# easyeda_dice.net
KiCad netlist of a schematic drawn in EasyEDA
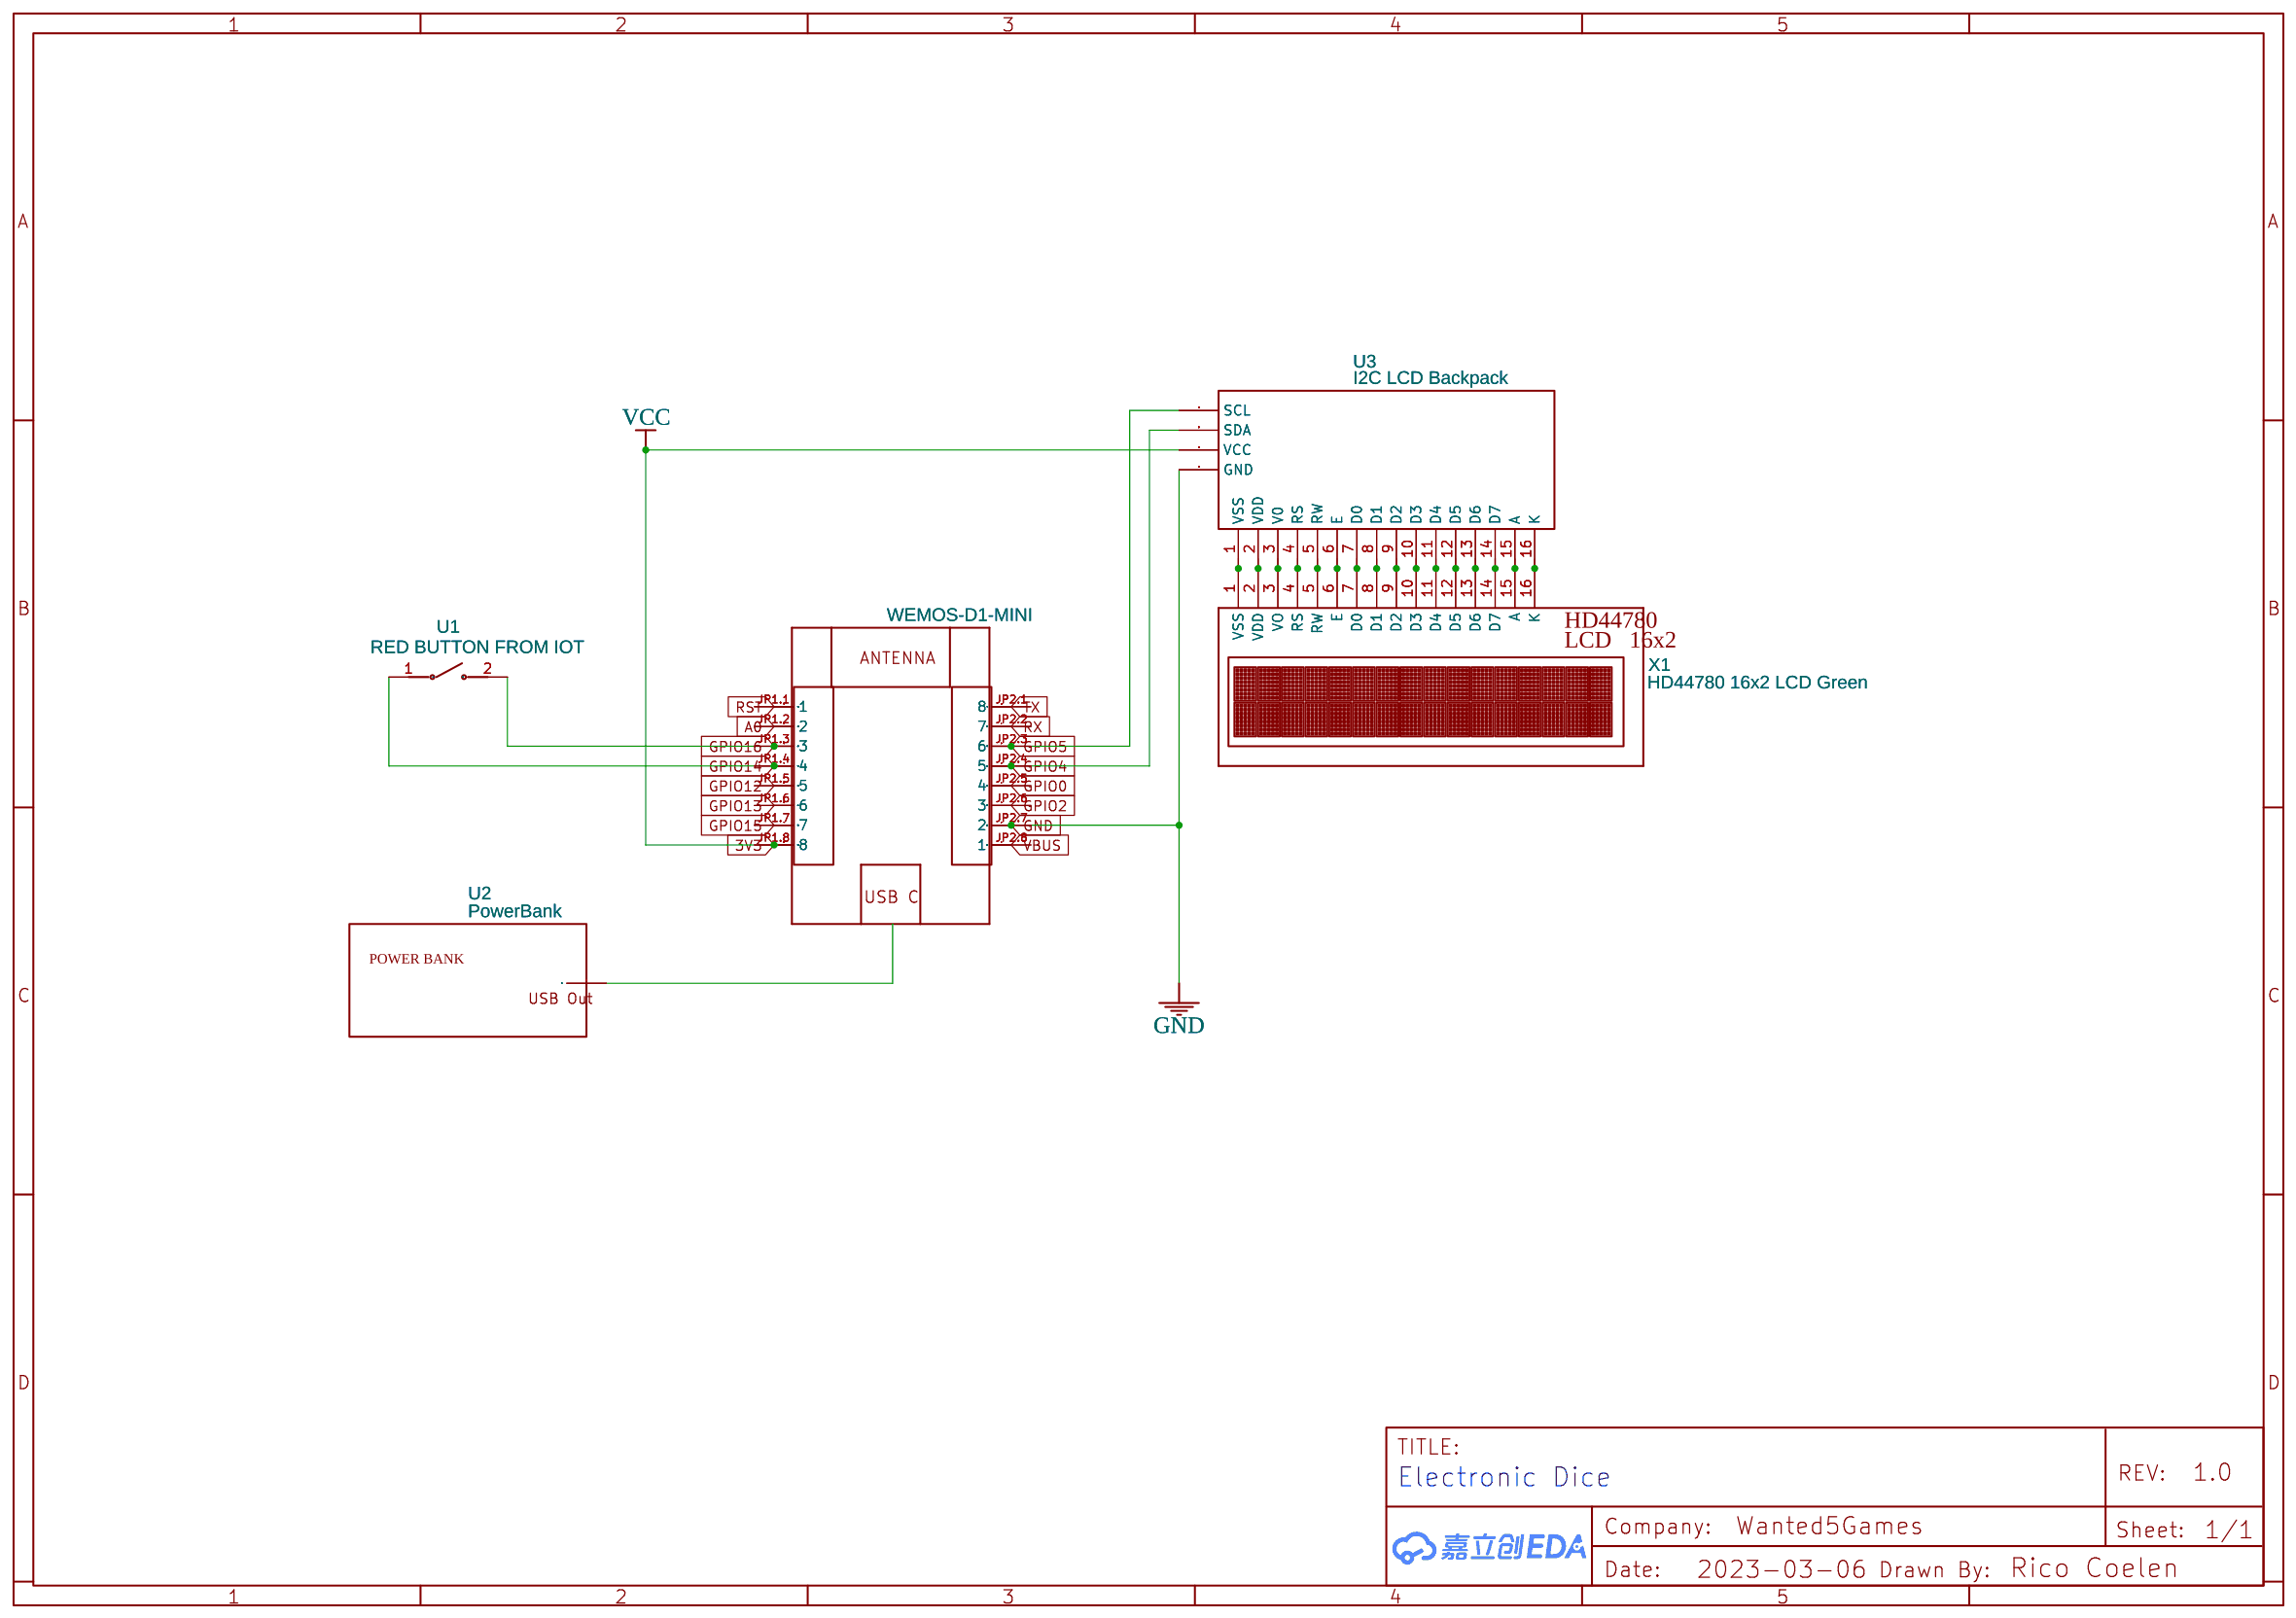
[diagram p0: schematic sheet]

(export (version "E")
  (design (tool "Eeschema 10.0.6"))
  (components
    (comp (ref "1") (value "WEMOS-D1-MINI") (libsource (lib "") (part "WEMOS-D1-MINI")))
    (comp (ref "H1")
      (value "HDR-F-2.54_1x8")
      (fields (field (name "BOM_Supplier Part") "C225505"))
      (libsource (lib "") (part "HDR-F-2.54_1x8_1"))
    )
    (comp (ref "H2")
      (value "HDR-F-2.54_1x8")
      (fields (field (name "BOM_Supplier Part") "C225505"))
      (libsource (lib "") (part "HDR-F-2.54_1x8"))
    )
    (comp (ref "U1")
      (value "RED BUTTON FROM IOT")
      (fields
        (field (name "BOM_Manufacturer Part") "BUTTON")
        (field (name "BOM_Supplier Part") "C9900015607")
      )
      (libsource (lib "") (part "BUTTON"))
    )
    (comp (ref "U2") (value "PowerBank") (libsource (lib "") (part "PowerBank")))
    (comp (ref "U3")
      (value "I2C LCD Backpack")
      (fields (field (name "BOM_Manufacturer Part") "I2C Bus Converter"))
      (libsource (lib "") (part "I2C LCD Backpack"))
    )
    (comp (ref "X1")
      (value "HD44780 16x2 LCD Green")
      (fields (field (name "BOM_Manufacturer Part") "HD44780U"))
      (libsource (lib "") (part "HD44780 16x2 LCD Green"))
    )
  )
  (nets
    (net (code "1") (name "3V3") (class "Default")
      (node (ref "H1") (pin "8") (pinfunction "8_8") (pintype "unspecified"))
      (node (ref "U3") (pin "18") (pinfunction "VCC_18") (pintype "unspecified"))
    )
    (net (code "2") (name "A0") (class "Default")
      (node (ref "H1") (pin "2") (pinfunction "2_2") (pintype "unspecified"))
    )
    (net (code "3") (name "GND") (class "Default")
      (node (ref "H2") (pin "2") (pinfunction "2_2") (pintype "unspecified"))
      (node (ref "U3") (pin "17") (pinfunction "GND_17") (pintype "unspecified"))
    )
    (net (code "4") (name "GPIO0") (class "Default")
      (node (ref "H2") (pin "4") (pinfunction "4_4") (pintype "unspecified"))
    )
    (net (code "5") (name "GPIO2") (class "Default")
      (node (ref "H2") (pin "3") (pinfunction "3_3") (pintype "unspecified"))
    )
    (net (code "6") (name "GPIO4") (class "Default")
      (node (ref "H2") (pin "5") (pinfunction "5_5") (pintype "unspecified"))
      (node (ref "U3") (pin "19") (pinfunction "SDA_19") (pintype "unspecified"))
    )
    (net (code "7") (name "GPIO5") (class "Default")
      (node (ref "H2") (pin "6") (pinfunction "6_6") (pintype "unspecified"))
      (node (ref "U3") (pin "20") (pinfunction "SCL_20") (pintype "unspecified"))
    )
    (net (code "8") (name "GPIO12") (class "Default")
      (node (ref "H1") (pin "5") (pinfunction "5_5") (pintype "unspecified"))
    )
    (net (code "9") (name "GPIO13") (class "Default")
      (node (ref "H1") (pin "6") (pinfunction "6_6") (pintype "unspecified"))
    )
    (net (code "10") (name "GPIO14") (class "Default")
      (node (ref "H1") (pin "4") (pinfunction "4_4") (pintype "unspecified"))
      (node (ref "U1") (pin "1") (pinfunction "1_1") (pintype "unspecified"))
    )
    (net (code "11") (name "GPIO15") (class "Default")
      (node (ref "H1") (pin "7") (pinfunction "7_7") (pintype "unspecified"))
    )
    (net (code "12") (name "GPIO16") (class "Default")
      (node (ref "H1") (pin "3") (pinfunction "3_3") (pintype "unspecified"))
      (node (ref "U1") (pin "2") (pinfunction "2_2") (pintype "unspecified"))
    )
    (net (code "13") (name "Net-(U3-A)") (class "Default")
      (node (ref "U3") (pin "15") (pinfunction "A_15") (pintype "unspecified"))
      (node (ref "X1") (pin "15") (pinfunction "A_15") (pintype "unspecified"))
    )
    (net (code "14") (name "Net-(U3-D0)") (class "Default")
      (node (ref "U3") (pin "7") (pinfunction "D0_7") (pintype "unspecified"))
      (node (ref "X1") (pin "7") (pinfunction "D0_7") (pintype "bidirectional"))
    )
    (net (code "15") (name "Net-(U3-D1)") (class "Default")
      (node (ref "U3") (pin "8") (pinfunction "D1_8") (pintype "unspecified"))
      (node (ref "X1") (pin "8") (pinfunction "D1_8") (pintype "bidirectional"))
    )
    (net (code "16") (name "Net-(U3-D2)") (class "Default")
      (node (ref "U3") (pin "9") (pinfunction "D2_9") (pintype "unspecified"))
      (node (ref "X1") (pin "9") (pinfunction "D2_9") (pintype "bidirectional"))
    )
    (net (code "17") (name "Net-(U3-D3)") (class "Default")
      (node (ref "U3") (pin "10") (pinfunction "D3_10") (pintype "unspecified"))
      (node (ref "X1") (pin "10") (pinfunction "D3_10") (pintype "bidirectional"))
    )
    (net (code "18") (name "Net-(U3-D4)") (class "Default")
      (node (ref "U3") (pin "11") (pinfunction "D4_11") (pintype "unspecified"))
      (node (ref "X1") (pin "11") (pinfunction "D4_11") (pintype "bidirectional"))
    )
    (net (code "19") (name "Net-(U3-D5)") (class "Default")
      (node (ref "U3") (pin "12") (pinfunction "D5_12") (pintype "unspecified"))
      (node (ref "X1") (pin "12") (pinfunction "D5_12") (pintype "bidirectional"))
    )
    (net (code "20") (name "Net-(U3-D6)") (class "Default")
      (node (ref "U3") (pin "13") (pinfunction "D6_13") (pintype "unspecified"))
      (node (ref "X1") (pin "13") (pinfunction "D6_13") (pintype "bidirectional"))
    )
    (net (code "21") (name "Net-(U3-D7)") (class "Default")
      (node (ref "U3") (pin "14") (pinfunction "D7_14") (pintype "unspecified"))
      (node (ref "X1") (pin "14") (pinfunction "D7_14") (pintype "bidirectional"))
    )
    (net (code "22") (name "Net-(U3-E)") (class "Default")
      (node (ref "U3") (pin "6") (pinfunction "E_6") (pintype "unspecified"))
      (node (ref "X1") (pin "6") (pinfunction "E_6") (pintype "bidirectional"))
    )
    (net (code "23") (name "Net-(U3-K)") (class "Default")
      (node (ref "U3") (pin "16") (pinfunction "K_16") (pintype "unspecified"))
      (node (ref "X1") (pin "16") (pinfunction "K_16") (pintype "unspecified"))
    )
    (net (code "24") (name "Net-(U3-RS)") (class "Default")
      (node (ref "U3") (pin "4") (pinfunction "RS_4") (pintype "unspecified"))
      (node (ref "X1") (pin "4") (pinfunction "RS_4") (pintype "bidirectional"))
    )
    (net (code "25") (name "Net-(U3-RW)") (class "Default")
      (node (ref "U3") (pin "5") (pinfunction "RW_5") (pintype "unspecified"))
      (node (ref "X1") (pin "5") (pinfunction "RW_5") (pintype "bidirectional"))
    )
    (net (code "26") (name "Net-(U3-V0)") (class "Default")
      (node (ref "U3") (pin "3") (pinfunction "V0_3") (pintype "unspecified"))
      (node (ref "X1") (pin "3") (pinfunction "VO_3") (pintype "passive"))
    )
    (net (code "27") (name "Net-(U3-VDD)") (class "Default")
      (node (ref "U3") (pin "2") (pinfunction "VDD_2") (pintype "unspecified"))
      (node (ref "X1") (pin "2") (pinfunction "VDD_2") (pintype "passive"))
    )
    (net (code "28") (name "Net-(U3-VSS)") (class "Default")
      (node (ref "U3") (pin "1") (pinfunction "VSS_1") (pintype "unspecified"))
      (node (ref "X1") (pin "1") (pinfunction "VSS_1") (pintype "passive"))
    )
    (net (code "29") (name "RST") (class "Default")
      (node (ref "H1") (pin "1") (pinfunction "1_1") (pintype "unspecified"))
    )
    (net (code "30") (name "RX") (class "Default")
      (node (ref "H2") (pin "7") (pinfunction "7_7") (pintype "unspecified"))
    )
    (net (code "31") (name "TX") (class "Default")
      (node (ref "H2") (pin "8") (pinfunction "8_8") (pintype "unspecified"))
    )
    (net (code "32") (name "VBUS") (class "Default")
      (node (ref "H2") (pin "1") (pinfunction "1_1") (pintype "unspecified"))
    )
    (net (code "33") (name "unconnected-(1-3V3-PadJP1.8)") (class "Default")
      (node (ref "1") (pin "JP1.8") (pinfunction "3V3_JP1.8") (pintype "bidirectional"))
    )
    (net (code "34") (name "unconnected-(1-5V-PadJP2.8)") (class "Default")
      (node (ref "1") (pin "JP2.8") (pinfunction "5V_JP2.8") (pintype "bidirectional"))
    )
    (net (code "35") (name "unconnected-(1-A0-PadJP1.2)") (class "Default")
      (node (ref "1") (pin "JP1.2") (pinfunction "A0_JP1.2") (pintype "bidirectional"))
    )
    (net (code "36") (name "unconnected-(1-D0-PadJP1.3)") (class "Default")
      (node (ref "1") (pin "JP1.3") (pinfunction "D0_JP1.3") (pintype "bidirectional"))
    )
    (net (code "37") (name "unconnected-(1-D1-PadJP2.3)") (class "Default")
      (node (ref "1") (pin "JP2.3") (pinfunction "D1_JP2.3") (pintype "bidirectional"))
    )
    (net (code "38") (name "unconnected-(1-D2-PadJP2.4)") (class "Default")
      (node (ref "1") (pin "JP2.4") (pinfunction "D2_JP2.4") (pintype "bidirectional"))
    )
    (net (code "39") (name "unconnected-(1-D3-PadJP2.5)") (class "Default")
      (node (ref "1") (pin "JP2.5") (pinfunction "D3_JP2.5") (pintype "bidirectional"))
    )
    (net (code "40") (name "unconnected-(1-D4-PadJP2.6)") (class "Default")
      (node (ref "1") (pin "JP2.6") (pinfunction "D4_JP2.6") (pintype "bidirectional"))
    )
    (net (code "41") (name "unconnected-(1-D5-PadJP1.4)") (class "Default")
      (node (ref "1") (pin "JP1.4") (pinfunction "D5_JP1.4") (pintype "bidirectional"))
    )
    (net (code "42") (name "unconnected-(1-D6-PadJP1.5)") (class "Default")
      (node (ref "1") (pin "JP1.5") (pinfunction "D6_JP1.5") (pintype "bidirectional"))
    )
    (net (code "43") (name "unconnected-(1-D7-PadJP1.6)") (class "Default")
      (node (ref "1") (pin "JP1.6") (pinfunction "D7_JP1.6") (pintype "bidirectional"))
    )
    (net (code "44") (name "unconnected-(1-D8-PadJP1.7)") (class "Default")
      (node (ref "1") (pin "JP1.7") (pinfunction "D8_JP1.7") (pintype "bidirectional"))
    )
    (net (code "45") (name "unconnected-(1-GND-PadJP2.7)") (class "Default")
      (node (ref "1") (pin "JP2.7") (pinfunction "GND_JP2.7") (pintype "bidirectional"))
    )
    (net (code "46") (name "unconnected-(1-RST-PadJP1.1)") (class "Default")
      (node (ref "1") (pin "JP1.1") (pinfunction "RST_JP1.1") (pintype "bidirectional"))
    )
    (net (code "47") (name "unconnected-(1-RX-PadJP2.2)") (class "Default")
      (node (ref "1") (pin "JP2.2") (pinfunction "RX_JP2.2") (pintype "bidirectional"))
    )
    (net (code "48") (name "unconnected-(1-TX-PadJP2.1)") (class "Default")
      (node (ref "1") (pin "JP2.1") (pinfunction "TX_JP2.1") (pintype "bidirectional"))
    )
    (net (code "49") (name "unconnected-(U2-Pad1)") (class "Default")
      (node (ref "U2") (pin "1") (pinfunction "1_1") (pintype "unspecified"))
    )
  )
)
